# REVERSE_PROTECTION.net
KiCad netlist of a schematic drawn in Altium Designer
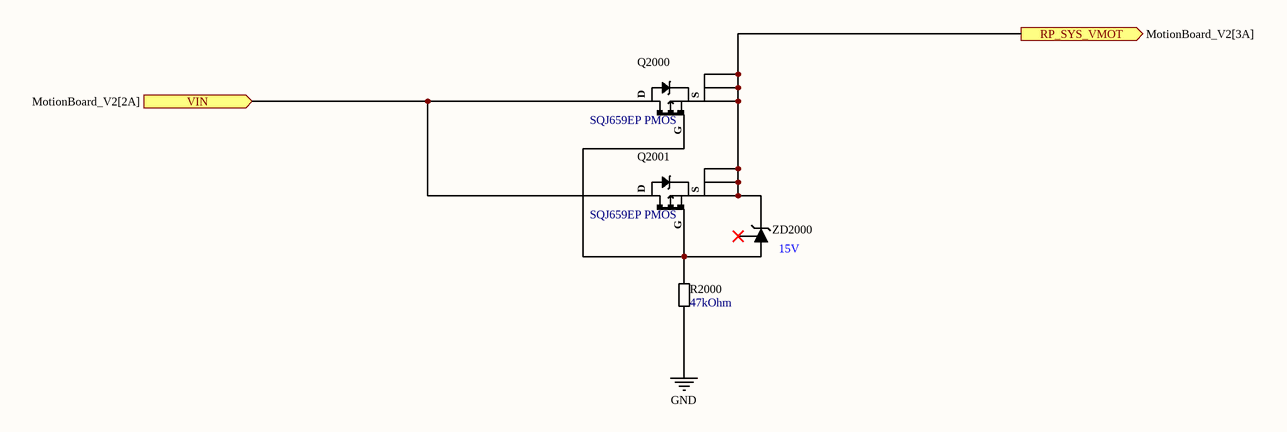
[diagram p0: REVERSE_PROTECTION.SchDoc]

(export (version "E")
  (design (tool "Eeschema 10.0.6"))
  (components
    (comp (ref "Q2000")
      (value "SQJ659EP PMOS")
      (footprint "PowerPAK SO-8L SINGLE")
      (description "P-Channel 60 V 52A (Tc) 83W (Tc) Surface Mount PowerPAK® SO-8")
      (fields
        (field (name "DIGIKEY PART NUMBER") "SQJ459EP-T1_GE3CT-ND")
        (field (name "MOUSER PART NUMBER") "78-SQJ459EP-T2_BE3")
      )
      (libsource (lib "Miscellaneous_Lib1") (part "00000005"))
    )
    (comp (ref "Q2001")
      (value "SQJ659EP PMOS")
      (footprint "PowerPAK SO-8L SINGLE")
      (description "P-Channel 60 V 52A (Tc) 83W (Tc) Surface Mount PowerPAK® SO-8")
      (fields
        (field (name "DIGIKEY PART NUMBER") "SQJ459EP-T1_GE3CT-ND")
        (field (name "MOUSER PART NUMBER") "78-SQJ459EP-T2_BE3")
      )
      (libsource (lib "Miscellaneous_Lib1") (part "00000005"))
    )
    (comp (ref "R2000")
      (value "47kOhm")
      (footprint "RES_0603")
      (description "47 kOhms ±1% 0.1W, 1/10W Chip Resistor 0603 (1608 Metric) Moisture Resistant Thick Film")
      (fields (field (name "DIGIKEY PART NUMBER") "311-47.0KHRCT-ND"))
      (libsource (lib "ResistorsIntegrated") (part "R000010"))
    )
    (comp (ref "ZD2000")
      (value "DZ23C15-E3-08 Zener Diode")
      (footprint "SOT95P245X96-3N")
      (description "Zener Diode Array 1 Pair Common Cathode 15 V 300 mW ±5% SOT-23-3")
      (fields (field (name "DIGIKEY PART NUMBER") "112-DZ23C15-E3-08CT-ND"))
      (libsource (lib "Miscellaneous_Lib1") (part "00000006"))
    )
  )
  (nets
    (net (code "1") (name "/RP_SYS_VMOT") (class "Default")
      (node (ref "Q2000") (pin "S") (pinfunction "S1_S") (pintype "passive"))
      (node (ref "Q2001") (pin "S") (pinfunction "S1_S") (pintype "passive"))
      (node (ref "ZD2000") (pin "3") (pinfunction "Cathode_3") (pintype "passive"))
    )
    (net (code "2") (name "/VIN") (class "Default")
      (node (ref "Q2000") (pin "D") (pinfunction "D_D") (pintype "passive"))
      (node (ref "Q2001") (pin "D") (pinfunction "D_D") (pintype "passive"))
    )
    (net (code "3") (name "GND") (class "Default")
      (node (ref "R2000") (pin "1") (pinfunction "1_1") (pintype "passive"))
    )
    (net (code "4") (name "Net-(Q2000-PadG)") (class "Default")
      (node (ref "Q2000") (pin "G") (pinfunction "G_G") (pintype "passive"))
      (node (ref "Q2001") (pin "G") (pinfunction "G_G") (pintype "passive"))
      (node (ref "R2000") (pin "2") (pinfunction "2_2") (pintype "passive"))
      (node (ref "ZD2000") (pin "1") (pinfunction "Anode_1") (pintype "passive"))
    )
    (net (code "5") (name "unconnected-(ZD2000-Anode-Pad2)") (class "Default")
      (node (ref "ZD2000") (pin "2") (pinfunction "Anode_2") (pintype "passive+no_connect"))
    )
  )
)
